# LooSensorNodeV0.net
KiCad netlist of a schematic drawn in EAGLE
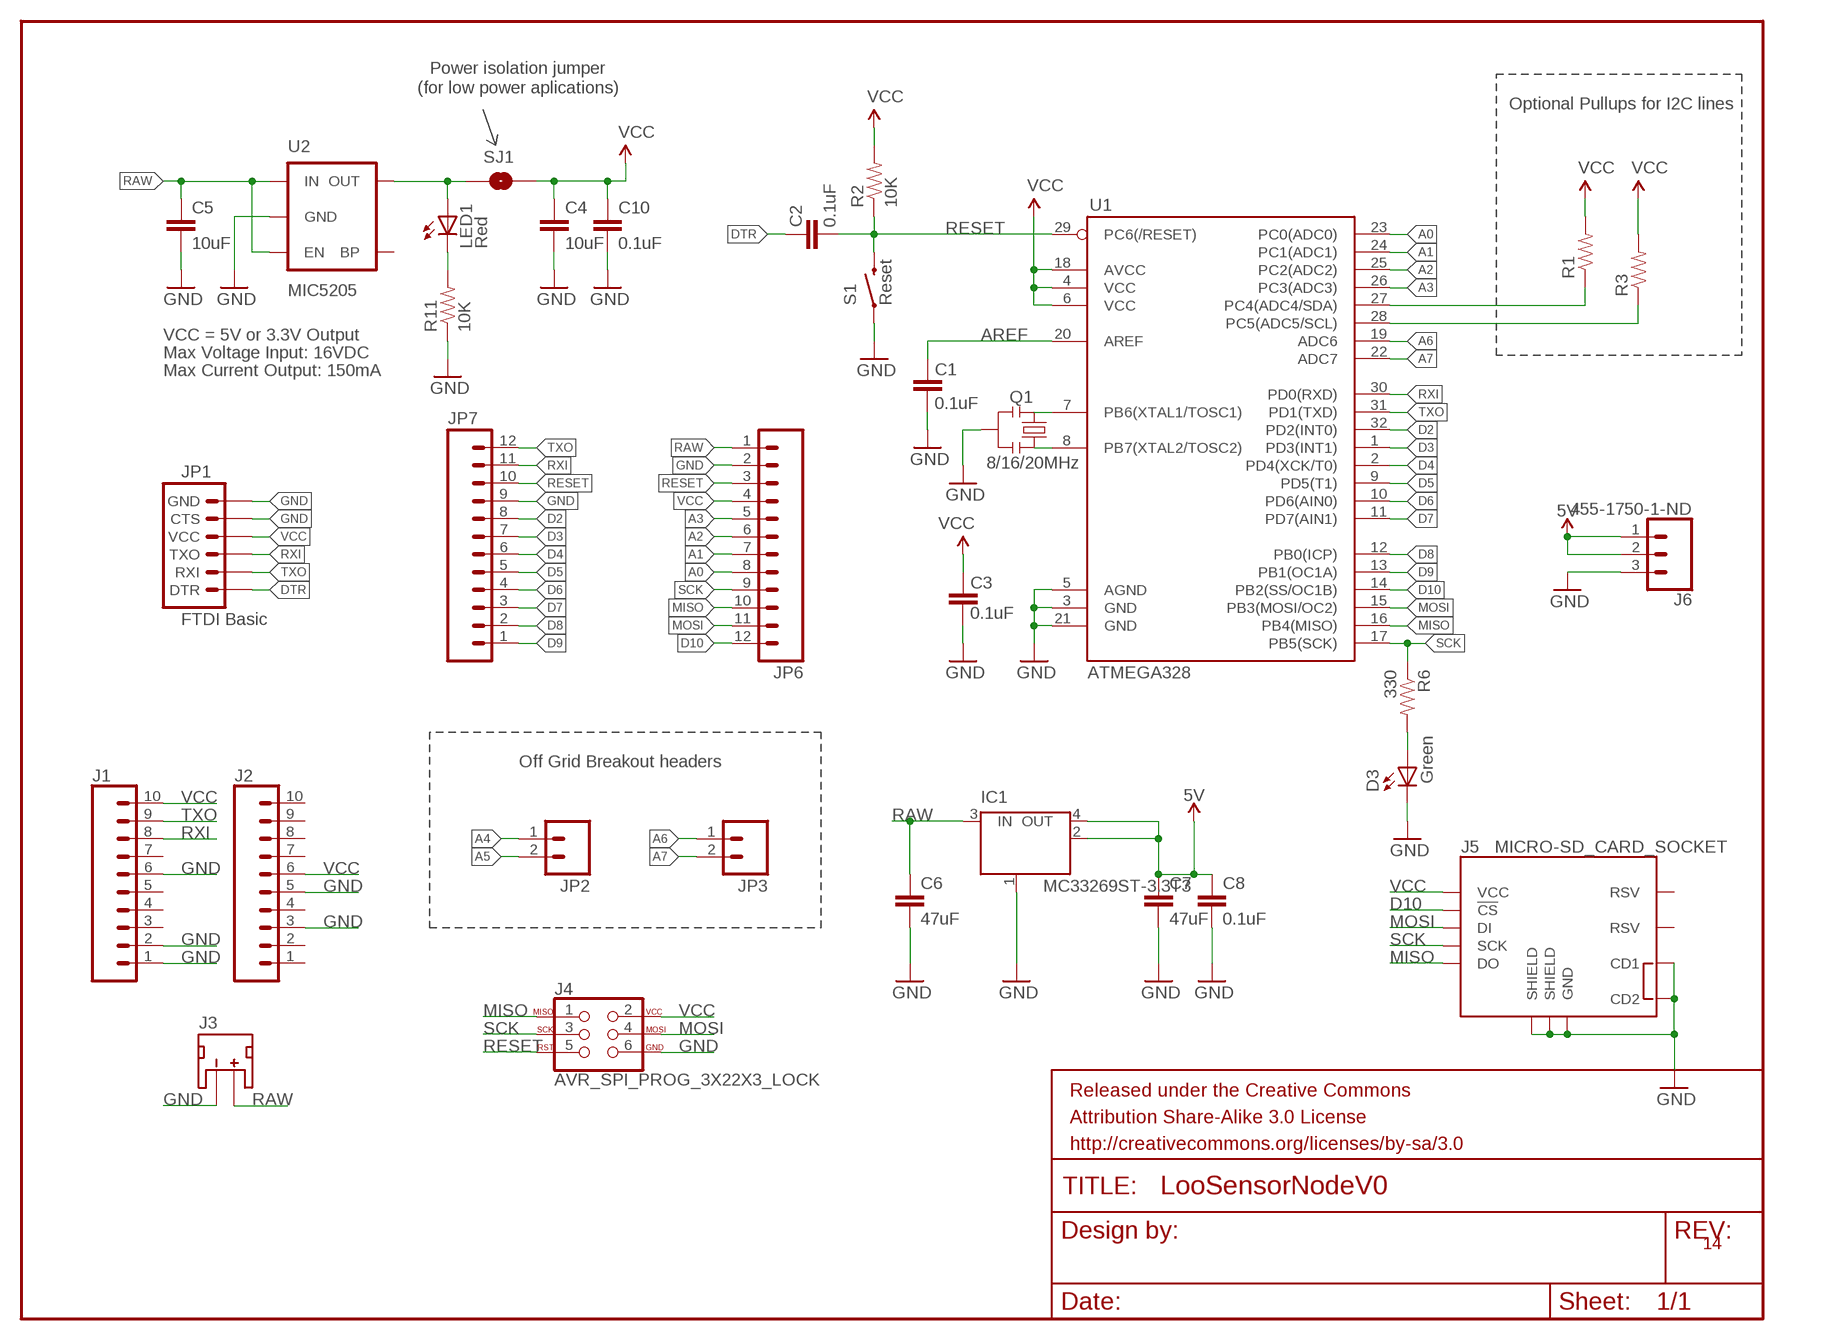
[diagram p0: schematic, sheet 1]

(export (version "E")
  (design (tool "Eeschema 10.0.6"))
  (components
    (comp (ref "C1")
      (value "0.1uF")
      (footprint "eagle-import:0603-CAP")
      (libsource (lib "eagle-import") (part "CAP0603-CAP"))
    )
    (comp (ref "C2")
      (value "0.1uF")
      (footprint "eagle-import:0603-CAP")
      (libsource (lib "eagle-import") (part "CAP0603-CAP"))
    )
    (comp (ref "C3")
      (value "0.1uF")
      (footprint "eagle-import:0603-CAP")
      (libsource (lib "eagle-import") (part "CAP0603-CAP"))
    )
    (comp (ref "C4")
      (value "10uF")
      (footprint "eagle-import:0603")
      (libsource (lib "eagle-import") (part "10UF-0603-6.3V-20%"))
    )
    (comp (ref "C5")
      (value "10uF")
      (footprint "eagle-import:0603")
      (libsource (lib "eagle-import") (part "10UF-0603-6.3V-20%"))
    )
    (comp (ref "C6")
      (value "47uF")
      (footprint "eagle-import:1210")
      (libsource (lib "eagle-import") (part "10UF-1210-50V-20%"))
    )
    (comp (ref "C7")
      (value "47uF")
      (footprint "eagle-import:1210")
      (libsource (lib "eagle-import") (part "10UF-1210-50V-20%"))
    )
    (comp (ref "C8")
      (value "0.1uF")
      (footprint "eagle-import:0603")
      (libsource (lib "eagle-import") (part "0.1UF-0603-25V-5%"))
    )
    (comp (ref "C10")
      (value "0.1uF")
      (footprint "eagle-import:0603-CAP")
      (libsource (lib "eagle-import") (part "CAP0603-CAP"))
    )
    (comp (ref "D3")
      (value "Green")
      (footprint "eagle-import:0603-LED-ALT1")
      (libsource (lib "eagle-import") (part "LED"))
    )
    (comp (ref "FRAME1")
      (value "FRAME-LETTER")
      (footprint "eagle-import:CREATIVE_COMMONS")
      (libsource (lib "eagle-import") (part "FRAME-LETTER"))
    )
    (comp (ref "IC1")
      (value "MC33269ST-3.3T3")
      (footprint "eagle-import:SOT223")
      (libsource (lib "eagle-import") (part "MC33269ST-3.3T3"))
    )
    (comp (ref "J1")
      (value "CONN_102MM")
      (footprint "eagle-import:1X10-2MM")
      (libsource (lib "eagle-import") (part "CONN_102MM"))
    )
    (comp (ref "J2")
      (value "CONN_102MM")
      (footprint "eagle-import:1X10-2MM")
      (libsource (lib "eagle-import") (part "CONN_102MM"))
    )
    (comp (ref "J3")
      (value "JST_2MM_MALE")
      (footprint "eagle-import:JST-2-SMD")
      (libsource (lib "eagle-import") (part "JST_2MM_MALE"))
    )
    (comp (ref "J4")
      (value "AVR_SPI_PROG_3X22X3_LOCK")
      (footprint "eagle-import:2X3_LOCK")
      (libsource (lib "eagle-import") (part "AVR_SPI_PROG_3X22X3_LOCK"))
    )
    (comp (ref "J5")
      (value "MICRO-SD_CARD_SOCKET")
      (footprint "eagle-import:MICRO-SD-SOCKET")
      (libsource (lib "eagle-import") (part "MICRO-SD_CARD_SOCKET"))
    )
    (comp (ref "J6")
      (value "455-1750-1-ND")
      (footprint "eagle-import:1X03")
      (libsource (lib "eagle-import") (part "CONN_03"))
    )
    (comp (ref "JP1")
      (value "FTDI Basic")
      (footprint "eagle-import:1X06")
      (libsource (lib "eagle-import") (part "ARDUINO_SERIAL_PROGRAMPTH"))
    )
    (comp (ref "JP2")
      (value "M02PTH")
      (footprint "eagle-import:1X02")
      (libsource (lib "eagle-import") (part "M02PTH"))
    )
    (comp (ref "JP3")
      (value "M02PTH")
      (footprint "eagle-import:1X02")
      (libsource (lib "eagle-import") (part "M02PTH"))
    )
    (comp (ref "JP6")
      (value "M12PTH")
      (footprint "eagle-import:1X12")
      (libsource (lib "eagle-import") (part "M12PTH"))
    )
    (comp (ref "JP7")
      (value "M12PTH")
      (footprint "eagle-import:1X12")
      (libsource (lib "eagle-import") (part "M12PTH"))
    )
    (comp (ref "LED1")
      (value "Red")
      (footprint "eagle-import:0603-LED-ALT1")
      (libsource (lib "eagle-import") (part "LED"))
    )
    (comp (ref "Q1")
      (value "8/16/20MHz")
      (footprint "eagle-import:RESONATOR-SMD-1_1")
      (libsource (lib "eagle-import") (part "RESONATOR1{colon}1"))
    )
    (comp (ref "R1")
      (value "RESISTOR0603-RES")
      (footprint "eagle-import:0603-RES")
      (libsource (lib "eagle-import") (part "RESISTOR0603-RES"))
    )
    (comp (ref "R2")
      (value "10K")
      (footprint "eagle-import:0603-RES")
      (libsource (lib "eagle-import") (part "RESISTOR0603-RES"))
    )
    (comp (ref "R3")
      (value "RESISTOR0603-RES")
      (footprint "eagle-import:0603-RES")
      (libsource (lib "eagle-import") (part "RESISTOR0603-RES"))
    )
    (comp (ref "R6")
      (value "330")
      (footprint "eagle-import:0603-RES")
      (libsource (lib "eagle-import") (part "RESISTOR0603-RES"))
    )
    (comp (ref "R11")
      (value "10K")
      (footprint "eagle-import:0603-RES")
      (libsource (lib "eagle-import") (part "RESISTOR0603-RES"))
    )
    (comp (ref "S1")
      (value "Reset")
      (footprint "eagle-import:TACTILE-SWITCH-SMD-ALT01")
      (libsource (lib "eagle-import") (part "SWITCH-MOMENTARY-2SMD-ALT01"))
    )
    (comp (ref "SJ1")
      (value "SOLDERJUMPERNC")
      (footprint "eagle-import:SJ_2S")
      (libsource (lib "eagle-import") (part "SOLDERJUMPERNC"))
    )
    (comp (ref "U1")
      (value "ATMEGA328")
      (footprint "eagle-import:TQFP32-08")
      (libsource (lib "eagle-import") (part "ATMEGA168"))
    )
    (comp (ref "U2")
      (value "MIC5205")
      (footprint "eagle-import:SOT23-5")
      (libsource (lib "eagle-import") (part "V_REG_LDOSMD"))
    )
  )
  (nets
    (net (code "1") (name "/AREF") (class "Default")
      (node (ref "C1") (pin "2") (pinfunction "2_2") (pintype "passive"))
      (node (ref "U1") (pin "20") (pinfunction "AREF_20") (pintype "bidirectional"))
    )
    (net (code "2") (name "5V") (class "Default")
      (node (ref "C7") (pin "1") (pinfunction "1_1") (pintype "passive"))
      (node (ref "C8") (pin "1") (pinfunction "1_1") (pintype "passive"))
      (node (ref "IC1") (pin "2") (pinfunction "OUT_2") (pintype "passive"))
      (node (ref "IC1") (pin "4") (pinfunction "OUT_4") (pintype "passive"))
      (node (ref "J6") (pin "1") (pinfunction "1_1") (pintype "passive"))
      (node (ref "J6") (pin "2") (pinfunction "2_2") (pintype "passive"))
    )
    (net (code "3") (name "A0") (class "Default")
      (node (ref "JP6") (pin "8") (pinfunction "8_8") (pintype "passive"))
      (node (ref "U1") (pin "23") (pinfunction "PC0(ADC0)_23") (pintype "bidirectional"))
    )
    (net (code "4") (name "A1") (class "Default")
      (node (ref "JP6") (pin "7") (pinfunction "7_7") (pintype "passive"))
      (node (ref "U1") (pin "24") (pinfunction "PC1(ADC1)_24") (pintype "bidirectional"))
    )
    (net (code "5") (name "A2") (class "Default")
      (node (ref "JP6") (pin "6") (pinfunction "6_6") (pintype "passive"))
      (node (ref "U1") (pin "25") (pinfunction "PC2(ADC2)_25") (pintype "bidirectional"))
    )
    (net (code "6") (name "A3") (class "Default")
      (node (ref "JP6") (pin "5") (pinfunction "5_5") (pintype "passive"))
      (node (ref "U1") (pin "26") (pinfunction "PC3(ADC3)_26") (pintype "bidirectional"))
    )
    (net (code "7") (name "A4") (class "Default")
      (node (ref "JP2") (pin "1") (pinfunction "1_1") (pintype "passive"))
      (node (ref "R1") (pin "1") (pinfunction "1_1") (pintype "passive"))
      (node (ref "U1") (pin "27") (pinfunction "PC4(ADC4/SDA)_27") (pintype "bidirectional"))
    )
    (net (code "8") (name "A5") (class "Default")
      (node (ref "JP2") (pin "2") (pinfunction "2_2") (pintype "passive"))
      (node (ref "R3") (pin "1") (pinfunction "1_1") (pintype "passive"))
      (node (ref "U1") (pin "28") (pinfunction "PC5(ADC5/SCL)_28") (pintype "bidirectional"))
    )
    (net (code "9") (name "A6") (class "Default")
      (node (ref "JP3") (pin "1") (pinfunction "1_1") (pintype "passive"))
      (node (ref "U1") (pin "19") (pinfunction "ADC6_19") (pintype "bidirectional"))
    )
    (net (code "10") (name "A7") (class "Default")
      (node (ref "JP3") (pin "2") (pinfunction "2_2") (pintype "passive"))
      (node (ref "U1") (pin "22") (pinfunction "ADC7_22") (pintype "bidirectional"))
    )
    (net (code "11") (name "D2") (class "Default")
      (node (ref "JP7") (pin "8") (pinfunction "8_8") (pintype "passive"))
      (node (ref "U1") (pin "32") (pinfunction "PD2(INT0)_32") (pintype "bidirectional"))
    )
    (net (code "12") (name "D3") (class "Default")
      (node (ref "JP7") (pin "7") (pinfunction "7_7") (pintype "passive"))
      (node (ref "U1") (pin "1") (pinfunction "PD3(INT1)_1") (pintype "bidirectional"))
    )
    (net (code "13") (name "D4") (class "Default")
      (node (ref "JP7") (pin "6") (pinfunction "6_6") (pintype "passive"))
      (node (ref "U1") (pin "2") (pinfunction "PD4(XCK/T0)_2") (pintype "bidirectional"))
    )
    (net (code "14") (name "D5") (class "Default")
      (node (ref "JP7") (pin "5") (pinfunction "5_5") (pintype "passive"))
      (node (ref "U1") (pin "9") (pinfunction "PD5(T1)_9") (pintype "bidirectional"))
    )
    (net (code "15") (name "D6") (class "Default")
      (node (ref "JP7") (pin "4") (pinfunction "4_4") (pintype "passive"))
      (node (ref "U1") (pin "10") (pinfunction "PD6(AIN0)_10") (pintype "bidirectional"))
    )
    (net (code "16") (name "D7") (class "Default")
      (node (ref "JP7") (pin "3") (pinfunction "3_3") (pintype "passive"))
      (node (ref "U1") (pin "11") (pinfunction "PD7(AIN1)_11") (pintype "bidirectional"))
    )
    (net (code "17") (name "D8") (class "Default")
      (node (ref "JP7") (pin "2") (pinfunction "2_2") (pintype "passive"))
      (node (ref "U1") (pin "12") (pinfunction "PB0(ICP)_12") (pintype "bidirectional"))
    )
    (net (code "18") (name "D9") (class "Default")
      (node (ref "JP7") (pin "1") (pinfunction "1_1") (pintype "passive"))
      (node (ref "U1") (pin "13") (pinfunction "PB1(OC1A)_13") (pintype "bidirectional"))
    )
    (net (code "19") (name "D10") (class "Default")
      (node (ref "J5") (pin "CS") (pinfunction "~{CS}_CS") (pintype "bidirectional"))
      (node (ref "JP6") (pin "12") (pinfunction "12_12") (pintype "passive"))
      (node (ref "U1") (pin "14") (pinfunction "PB2(SS/OC1B)_14") (pintype "bidirectional"))
    )
    (net (code "20") (name "DTR") (class "Default")
      (node (ref "C2") (pin "2") (pinfunction "2_2") (pintype "passive"))
      (node (ref "JP1") (pin "1") (pinfunction "DTR_1") (pintype "passive"))
    )
    (net (code "21") (name "GND") (class "Default")
      (node (ref "C1") (pin "1") (pinfunction "1_1") (pintype "passive"))
      (node (ref "C10") (pin "2") (pinfunction "2_2") (pintype "passive"))
      (node (ref "C3") (pin "1") (pinfunction "1_1") (pintype "passive"))
      (node (ref "C4") (pin "2") (pinfunction "2_2") (pintype "passive"))
      (node (ref "C5") (pin "2") (pinfunction "2_2") (pintype "passive"))
      (node (ref "C6") (pin "2") (pinfunction "2_2") (pintype "passive"))
      (node (ref "C7") (pin "2") (pinfunction "2_2") (pintype "passive"))
      (node (ref "C8") (pin "2") (pinfunction "2_2") (pintype "passive"))
      (node (ref "D3") (pin "C") (pinfunction "C_C") (pintype "passive"))
      (node (ref "IC1") (pin "1") (pinfunction "GND/ADJ_1") (pintype "input"))
      (node (ref "J1") (pin "1") (pinfunction "1_1") (pintype "passive"))
      (node (ref "J1") (pin "2") (pinfunction "2_2") (pintype "passive"))
      (node (ref "J1") (pin "6") (pinfunction "6_6") (pintype "passive"))
      (node (ref "J2") (pin "3") (pinfunction "3_3") (pintype "passive"))
      (node (ref "J2") (pin "5") (pinfunction "5_5") (pintype "passive"))
      (node (ref "J3") (pin "1") (pinfunction "-_1") (pintype "bidirectional"))
      (node (ref "J4") (pin "6") (pinfunction "6_6") (pintype "passive"))
      (node (ref "J5") (pin "CD1") (pinfunction "CD1_CD1") (pintype "bidirectional"))
      (node (ref "J5") (pin "CD2") (pinfunction "CD2_CD2") (pintype "bidirectional"))
      (node (ref "J5") (pin "GND") (pinfunction "GND_GND") (pintype "bidirectional"))
      (node (ref "J5") (pin "GND1") (pinfunction "SHIELD_GND1") (pintype "bidirectional"))
      (node (ref "J5") (pin "GND3") (pinfunction "SHIELD_GND3") (pintype "bidirectional"))
      (node (ref "J6") (pin "3") (pinfunction "3_3") (pintype "passive"))
      (node (ref "JP1") (pin "5") (pinfunction "CTS_5") (pintype "passive"))
      (node (ref "JP1") (pin "6") (pinfunction "GND_6") (pintype "passive"))
      (node (ref "JP6") (pin "2") (pinfunction "2_2") (pintype "passive"))
      (node (ref "JP7") (pin "9") (pinfunction "9_9") (pintype "passive"))
      (node (ref "Q1") (pin "2") (pinfunction "2_2") (pintype "passive"))
      (node (ref "R11") (pin "1") (pinfunction "1_1") (pintype "passive"))
      (node (ref "S1") (pin "1") (pinfunction "1_1") (pintype "passive"))
      (node (ref "S1") (pin "2") (pinfunction "1_2") (pintype "passive"))
      (node (ref "U1") (pin "21") (pinfunction "GND_21") (pintype "bidirectional"))
      (node (ref "U1") (pin "3") (pinfunction "GND_3") (pintype "bidirectional"))
      (node (ref "U1") (pin "5") (pinfunction "AGND_5") (pintype "bidirectional"))
      (node (ref "U2") (pin "2") (pinfunction "GND_2") (pintype "input"))
    )
    (net (code "22") (name "MISO") (class "Default")
      (node (ref "J4") (pin "1") (pinfunction "1_1") (pintype "passive"))
      (node (ref "J5") (pin "DO") (pinfunction "DO_DO") (pintype "bidirectional"))
      (node (ref "JP6") (pin "10") (pinfunction "10_10") (pintype "passive"))
      (node (ref "U1") (pin "16") (pinfunction "PB4(MISO)_16") (pintype "bidirectional"))
    )
    (net (code "23") (name "MOSI") (class "Default")
      (node (ref "J4") (pin "4") (pinfunction "4_4") (pintype "passive"))
      (node (ref "J5") (pin "DI") (pinfunction "DI_DI") (pintype "bidirectional"))
      (node (ref "JP6") (pin "11") (pinfunction "11_11") (pintype "passive"))
      (node (ref "U1") (pin "15") (pinfunction "PB3(MOSI/OC2)_15") (pintype "bidirectional"))
    )
    (net (code "24") (name "Net-(D3-PadA)") (class "Default")
      (node (ref "D3") (pin "A") (pinfunction "A_A") (pintype "passive"))
      (node (ref "R6") (pin "2") (pinfunction "2_2") (pintype "passive"))
    )
    (net (code "25") (name "Net-(LED1-PadC)") (class "Default")
      (node (ref "LED1") (pin "C") (pinfunction "C_C") (pintype "passive"))
      (node (ref "R11") (pin "2") (pinfunction "2_2") (pintype "passive"))
    )
    (net (code "26") (name "Net-(U1-PB6(XTAL1{slash}TOSC1))") (class "Default")
      (node (ref "Q1") (pin "1") (pinfunction "1_1") (pintype "passive"))
      (node (ref "U1") (pin "7") (pinfunction "PB6(XTAL1/TOSC1)_7") (pintype "bidirectional"))
    )
    (net (code "27") (name "Net-(U1-PB7(XTAL2{slash}TOSC2))") (class "Default")
      (node (ref "Q1") (pin "3") (pinfunction "3_3") (pintype "passive"))
      (node (ref "U1") (pin "8") (pinfunction "PB7(XTAL2/TOSC2)_8") (pintype "bidirectional"))
    )
    (net (code "28") (name "Net-(U2-OUT)") (class "Default")
      (node (ref "LED1") (pin "A") (pinfunction "A_A") (pintype "passive"))
      (node (ref "SJ1") (pin "1") (pinfunction "1_1") (pintype "passive"))
      (node (ref "U2") (pin "5") (pinfunction "OUT_5") (pintype "passive"))
    )
    (net (code "29") (name "RAW") (class "Default")
      (node (ref "C5") (pin "1") (pinfunction "1_1") (pintype "passive"))
      (node (ref "C6") (pin "1") (pinfunction "1_1") (pintype "passive"))
      (node (ref "IC1") (pin "3") (pinfunction "IN_3") (pintype "input"))
      (node (ref "J3") (pin "2") (pinfunction "+_2") (pintype "bidirectional"))
      (node (ref "JP6") (pin "1") (pinfunction "1_1") (pintype "passive"))
      (node (ref "U2") (pin "1") (pinfunction "IN_1") (pintype "input"))
      (node (ref "U2") (pin "3") (pinfunction "EN_3") (pintype "input"))
    )
    (net (code "30") (name "RESET") (class "Default")
      (node (ref "C2") (pin "1") (pinfunction "1_1") (pintype "passive"))
      (node (ref "J4") (pin "5") (pinfunction "5_5") (pintype "passive"))
      (node (ref "JP6") (pin "3") (pinfunction "3_3") (pintype "passive"))
      (node (ref "JP7") (pin "10") (pinfunction "10_10") (pintype "passive"))
      (node (ref "R2") (pin "1") (pinfunction "1_1") (pintype "passive"))
      (node (ref "S1") (pin "3") (pinfunction "2_3") (pintype "passive"))
      (node (ref "S1") (pin "4") (pinfunction "2_4") (pintype "passive"))
      (node (ref "U1") (pin "29") (pinfunction "PC6(/RESET)_29") (pintype "bidirectional"))
    )
    (net (code "31") (name "RXI") (class "Default")
      (node (ref "J1") (pin "8") (pinfunction "8_8") (pintype "passive"))
      (node (ref "JP1") (pin "3") (pinfunction "TXO_3") (pintype "passive"))
      (node (ref "JP7") (pin "11") (pinfunction "11_11") (pintype "passive"))
      (node (ref "U1") (pin "30") (pinfunction "PD0(RXD)_30") (pintype "bidirectional"))
    )
    (net (code "32") (name "SCK") (class "Default")
      (node (ref "J4") (pin "3") (pinfunction "3_3") (pintype "passive"))
      (node (ref "J5") (pin "SCLK") (pinfunction "SCK_SCLK") (pintype "bidirectional"))
      (node (ref "JP6") (pin "9") (pinfunction "9_9") (pintype "passive"))
      (node (ref "R6") (pin "1") (pinfunction "1_1") (pintype "passive"))
      (node (ref "U1") (pin "17") (pinfunction "PB5(SCK)_17") (pintype "bidirectional"))
    )
    (net (code "33") (name "TXO") (class "Default")
      (node (ref "J1") (pin "9") (pinfunction "9_9") (pintype "passive"))
      (node (ref "JP1") (pin "2") (pinfunction "RXI_2") (pintype "passive"))
      (node (ref "JP7") (pin "12") (pinfunction "12_12") (pintype "passive"))
      (node (ref "U1") (pin "31") (pinfunction "PD1(TXD)_31") (pintype "bidirectional"))
    )
    (net (code "34") (name "VCC") (class "Default")
      (node (ref "C10") (pin "1") (pinfunction "1_1") (pintype "passive"))
      (node (ref "C3") (pin "2") (pinfunction "2_2") (pintype "passive"))
      (node (ref "C4") (pin "1") (pinfunction "1_1") (pintype "passive"))
      (node (ref "J1") (pin "10") (pinfunction "10_10") (pintype "passive"))
      (node (ref "J2") (pin "6") (pinfunction "6_6") (pintype "passive"))
      (node (ref "J4") (pin "2") (pinfunction "2_2") (pintype "passive"))
      (node (ref "J5") (pin "VCC") (pinfunction "VCC_VCC") (pintype "bidirectional"))
      (node (ref "JP1") (pin "4") (pinfunction "VCC_4") (pintype "passive"))
      (node (ref "JP6") (pin "4") (pinfunction "4_4") (pintype "passive"))
      (node (ref "R1") (pin "2") (pinfunction "2_2") (pintype "passive"))
      (node (ref "R2") (pin "2") (pinfunction "2_2") (pintype "passive"))
      (node (ref "R3") (pin "2") (pinfunction "2_2") (pintype "passive"))
      (node (ref "SJ1") (pin "2") (pinfunction "2_2") (pintype "passive"))
      (node (ref "U1") (pin "18") (pinfunction "AVCC_18") (pintype "bidirectional"))
      (node (ref "U1") (pin "4") (pinfunction "VCC_4") (pintype "bidirectional"))
      (node (ref "U1") (pin "6") (pinfunction "VCC_6") (pintype "bidirectional"))
    )
    (net (code "35") (name "unconnected-(J1-Pad3)") (class "Default")
      (node (ref "J1") (pin "3") (pinfunction "3_3") (pintype "passive"))
    )
    (net (code "36") (name "unconnected-(J1-Pad4)") (class "Default")
      (node (ref "J1") (pin "4") (pinfunction "4_4") (pintype "passive"))
    )
    (net (code "37") (name "unconnected-(J1-Pad5)") (class "Default")
      (node (ref "J1") (pin "5") (pinfunction "5_5") (pintype "passive"))
    )
    (net (code "38") (name "unconnected-(J1-Pad7)") (class "Default")
      (node (ref "J1") (pin "7") (pinfunction "7_7") (pintype "passive"))
    )
    (net (code "39") (name "unconnected-(J2-Pad1)") (class "Default")
      (node (ref "J2") (pin "1") (pinfunction "1_1") (pintype "passive"))
    )
    (net (code "40") (name "unconnected-(J2-Pad2)") (class "Default")
      (node (ref "J2") (pin "2") (pinfunction "2_2") (pintype "passive"))
    )
    (net (code "41") (name "unconnected-(J2-Pad4)") (class "Default")
      (node (ref "J2") (pin "4") (pinfunction "4_4") (pintype "passive"))
    )
    (net (code "42") (name "unconnected-(J2-Pad7)") (class "Default")
      (node (ref "J2") (pin "7") (pinfunction "7_7") (pintype "passive"))
    )
    (net (code "43") (name "unconnected-(J2-Pad8)") (class "Default")
      (node (ref "J2") (pin "8") (pinfunction "8_8") (pintype "passive"))
    )
    (net (code "44") (name "unconnected-(J2-Pad9)") (class "Default")
      (node (ref "J2") (pin "9") (pinfunction "9_9") (pintype "passive"))
    )
    (net (code "45") (name "unconnected-(J2-Pad10)") (class "Default")
      (node (ref "J2") (pin "10") (pinfunction "10_10") (pintype "passive"))
    )
    (net (code "46") (name "unconnected-(J3-PAD1-PadNC1)") (class "Default")
      (node (ref "J3") (pin "NC1") (pinfunction "PAD1_NC1") (pintype "bidirectional"))
    )
    (net (code "47") (name "unconnected-(J3-PAD2-PadNC2)") (class "Default")
      (node (ref "J3") (pin "NC2") (pinfunction "PAD2_NC2") (pintype "bidirectional"))
    )
    (net (code "48") (name "unconnected-(J5-RSV-PadRSV1)") (class "Default")
      (node (ref "J5") (pin "RSV1") (pinfunction "RSV_RSV1") (pintype "bidirectional"))
    )
    (net (code "49") (name "unconnected-(J5-RSV-PadRSV2)") (class "Default")
      (node (ref "J5") (pin "RSV2") (pinfunction "RSV_RSV2") (pintype "bidirectional"))
    )
    (net (code "50") (name "unconnected-(U2-BP-Pad4)") (class "Default")
      (node (ref "U2") (pin "4") (pinfunction "BP_4") (pintype "input"))
    )
  )
)
